# AmbaSat-08-GPS_TESEO.net
KiCad netlist of a schematic drawn in EAGLE
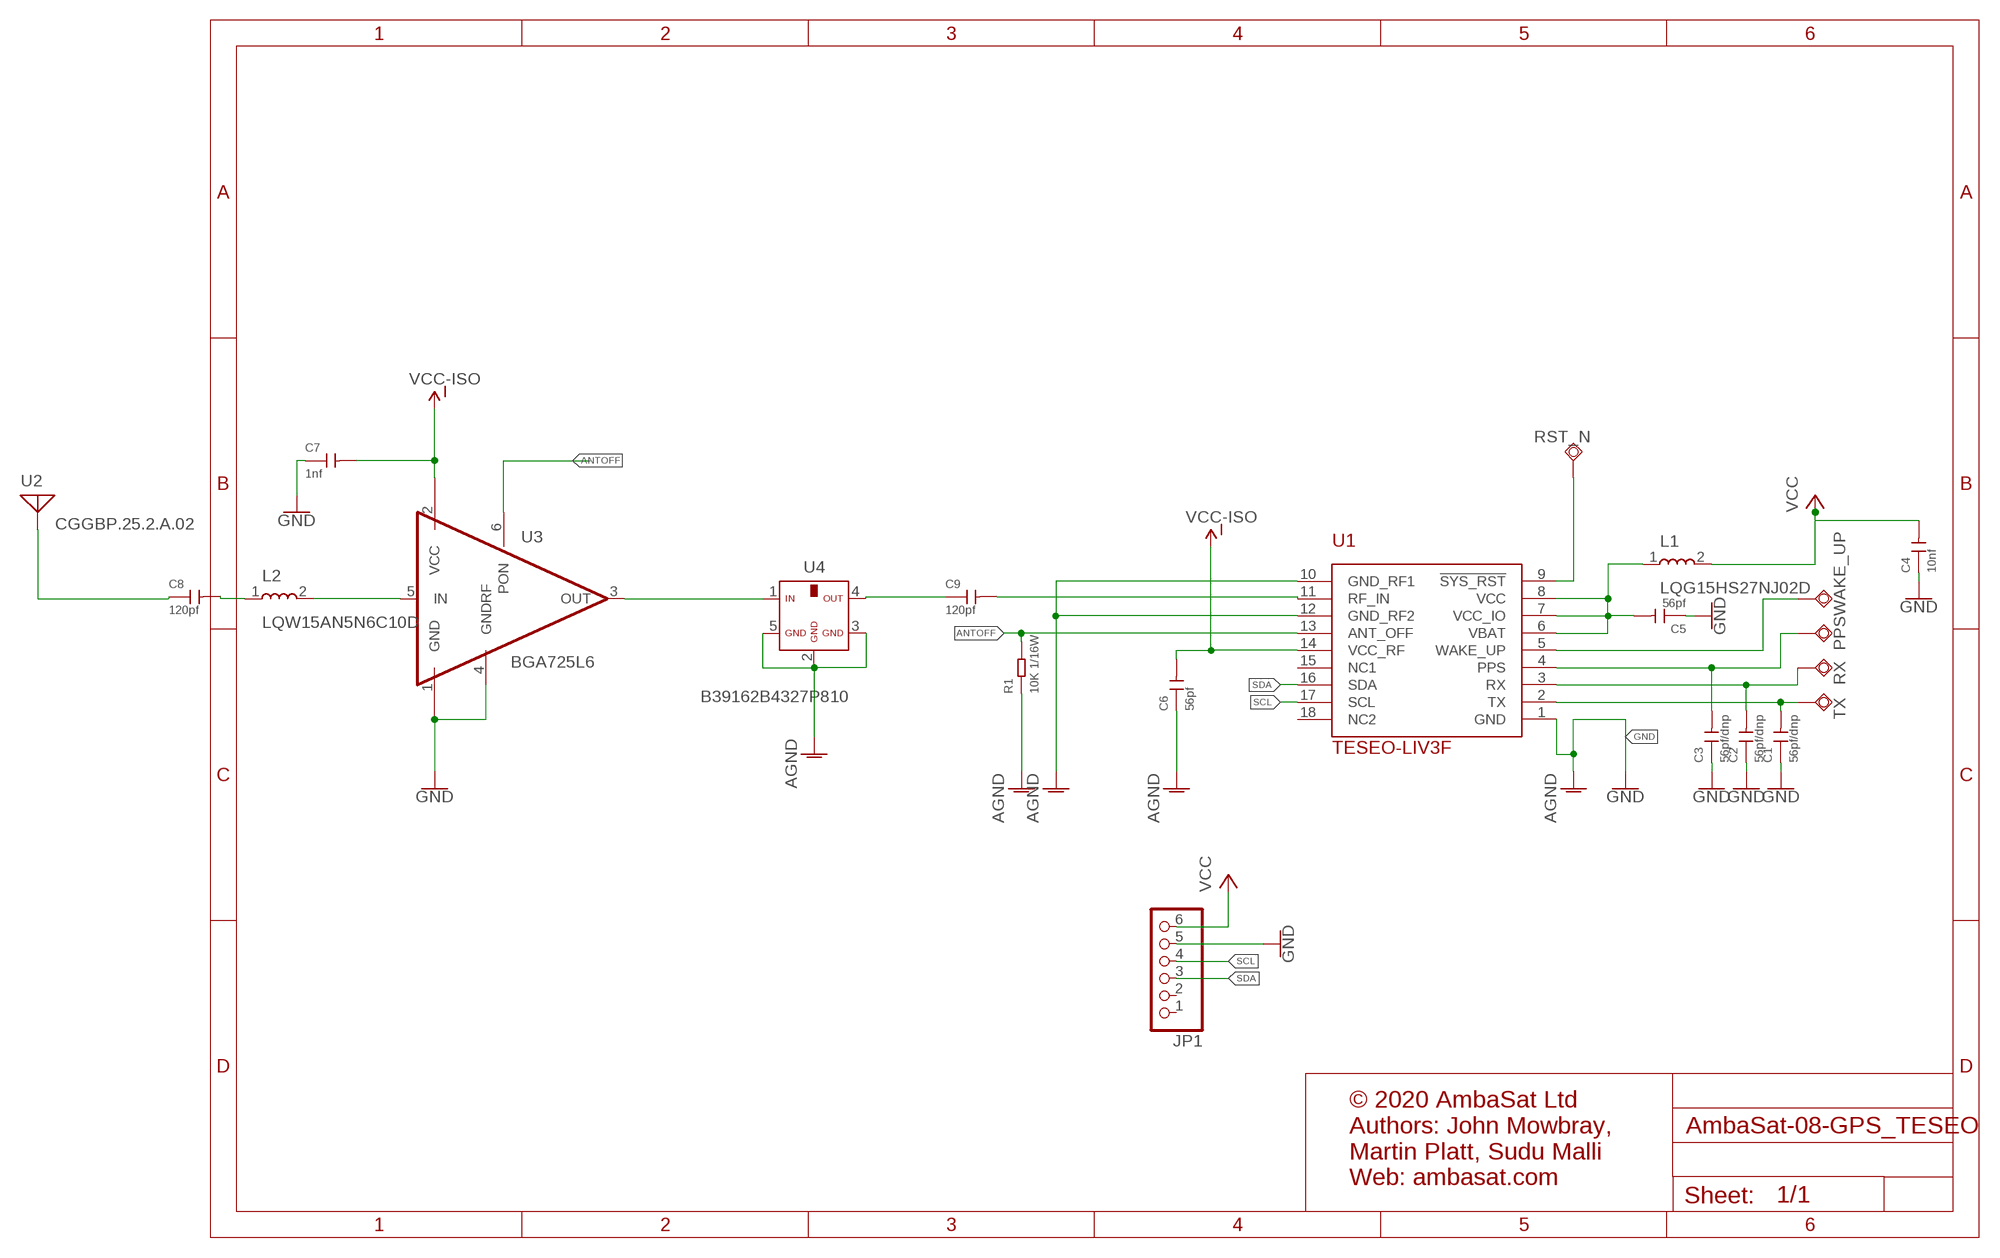
[diagram p0: schematic, sheet 1]

(export (version "E")
  (design (tool "Eeschema 10.0.6"))
  (components
    (comp (ref "C1")
      (value "56pf/dnp")
      (footprint "eagle-import:C0402")
      (fields (field (name "MPN") "CC0402JRNPO9BN101") (field (name "MPN_1") "CC0402JRNPO9BN560"))
      (libsource (lib "eagle-import") (part "CERAMIC-100PF-50V-5%-NPO(0402)"))
    )
    (comp (ref "C2")
      (value "56pf/dnp")
      (footprint "eagle-import:C0402")
      (fields (field (name "MPN") "CC0402JRNPO9BN101") (field (name "MPN_1") "CC0402JRNPO9BN560"))
      (libsource (lib "eagle-import") (part "CERAMIC-100PF-50V-5%-NPO(0402)"))
    )
    (comp (ref "C3")
      (value "56pf/dnp")
      (footprint "eagle-import:C0402")
      (fields (field (name "MPN") "CC0402JRNPO9BN101") (field (name "MPN_1") "CC0402JRNPO9BN560"))
      (libsource (lib "eagle-import") (part "CERAMIC-100PF-50V-5%-NPO(0402)"))
    )
    (comp (ref "C4")
      (value "10nf")
      (footprint "eagle-import:C0402")
      (fields (field (name "MPN") "CC0402KRX7R9BB103"))
      (libsource (lib "eagle-import") (part "CERAMIC-10NF-50V-10%-X7R(0402)"))
    )
    (comp (ref "C5")
      (value "56pf")
      (footprint "eagle-import:C0402")
      (fields (field (name "MPN") "CC0402JRNPO9BN101") (field (name "MPN_1") "CC0402JRNPO9BN560"))
      (libsource (lib "eagle-import") (part "CERAMIC-100PF-50V-5%-NPO(0402)"))
    )
    (comp (ref "C6")
      (value "56pf")
      (footprint "eagle-import:C0402")
      (fields (field (name "MPN") "CC0402JRNPO9BN101") (field (name "MPN_1") "CC0402JRNPO9BN560"))
      (libsource (lib "eagle-import") (part "CERAMIC-100PF-50V-5%-NPO(0402)"))
    )
    (comp (ref "C7")
      (value "1nf")
      (footprint "eagle-import:C0402")
      (fields (field (name "MPN") "CC0402KRX7R9BB102"))
      (libsource (lib "eagle-import") (part "CERAMIC-1NF-50V-10%-X7R(0402)"))
    )
    (comp (ref "C8")
      (value "120pf")
      (footprint "eagle-import:C0402")
      (fields (field (name "MPN") "CC0402JRNPO9BN101") (field (name "MPN_1") "CC0402JRNPO9BN121"))
      (libsource (lib "eagle-import") (part "CERAMIC-100PF-50V-5%-NPO(0402)"))
    )
    (comp (ref "C9")
      (value "120pf")
      (footprint "eagle-import:C0402")
      (fields (field (name "MPN") "CC0402JRNPO9BN101") (field (name "MPN_1") "CC0402JRNPO9BN121"))
      (libsource (lib "eagle-import") (part "CERAMIC-100PF-50V-5%-NPO(0402)"))
    )
    (comp (ref "JP1")
      (value "HEADER-1X6")
      (footprint "eagle-import:1X06_OVAL")
      (libsource (lib "eagle-import") (part "HEADER-1X6"))
    )
    (comp (ref "L1")
      (value "LQG15HS27NJ02D")
      (footprint "eagle-import:LQG15HN2N2S02D")
      (fields
        (field (name "DIGIKEY_PART_NUMBER") "490-1077-2-ND")
        (field (name "MANUFACTURER") "Murata Electronics North America")
        (field (name "MPN") "LQG15HN2N2S02D")
        (field (name "DIGIKEY_PART_NUMBER_1") "490-2628-1-ND")
        (field (name "MPN_1") "LQG15HS27NJ02D")
        (field (name "CREATED_BY") "PCBLayout.com")
      )
      (libsource (lib "eagle-import") (part "LQG15HN2N2S02D"))
    )
    (comp (ref "L2")
      (value "LQW15AN5N6C10D")
      (footprint "eagle-import:LQG15HN2N2S02D")
      (fields
        (field (name "DIGIKEY_PART_NUMBER") "490-1077-2-ND")
        (field (name "MANUFACTURER") "Murata Electronics North America")
        (field (name "MPN") "LQG15HN2N2S02D")
        (field (name "DIGIKEY_PART_NUMBER_1") "490-6833-1-ND")
        (field (name "MPN_1") "LQW15AN5N6C10D")
        (field (name "CREATED_BY") "PCBLayout.com")
      )
      (libsource (lib "eagle-import") (part "LQG15HN2N2S02D"))
    )
    (comp (ref "PPS")
      (value "TESTPAD_TPSQTP11SQ")
      (footprint "eagle-import:TESTPAD_TP11SQ")
      (libsource (lib "eagle-import") (part "TESTPAD_TPSQTP11SQ"))
    )
    (comp (ref "R1")
      (value "10K 1/16W")
      (footprint "eagle-import:R0402")
      (fields (field (name "MPN") "RC0402FR-0710KL"))
      (libsource (lib "eagle-import") (part "SMD-RES-10K-1%-1/16W(0402)"))
    )
    (comp (ref "RST_N")
      (value "TESTPAD_TPSQTP11SQ")
      (footprint "eagle-import:TESTPAD_TP11SQ")
      (libsource (lib "eagle-import") (part "TESTPAD_TPSQTP11SQ"))
    )
    (comp (ref "RX")
      (value "TESTPAD_TPSQTP11SQ")
      (footprint "eagle-import:TESTPAD_TP11SQ")
      (libsource (lib "eagle-import") (part "TESTPAD_TPSQTP11SQ"))
    )
    (comp (ref "TX")
      (value "TESTPAD_TPSQTP11SQ")
      (footprint "eagle-import:TESTPAD_TP11SQ")
      (libsource (lib "eagle-import") (part "TESTPAD_TPSQTP11SQ"))
    )
    (comp (ref "U1")
      (value "TESEO-LIV3F")
      (footprint "eagle-import:TESEO-LIV3F")
      (libsource (lib "eagle-import") (part "TESEO-LIV3F"))
    )
    (comp (ref "U2")
      (value "CGGBP.25.2.A.02")
      (footprint "eagle-import:ANTENNA-PATCH")
      (libsource (lib "eagle-import") (part "CGGBP.25.2.A.02"))
    )
    (comp (ref "U3")
      (value "BGA725L6")
      (footprint "eagle-import:PSON35P100X100X35-6N")
      (fields (field (name "MPN") "BGA725L6E6327FTSA1"))
      (libsource (lib "eagle-import") (part "BGA725L6"))
    )
    (comp (ref "U4")
      (value "B39162B4327P810")
      (footprint "eagle-import:FIL_B39162B9417K610")
      (libsource (lib "eagle-import") (part "B39162B4327P810"))
    )
    (comp (ref "WAKE_UP")
      (value "TESTPAD_TPSQTP11SQ")
      (footprint "eagle-import:TESTPAD_TP11SQ")
      (libsource (lib "eagle-import") (part "TESTPAD_TPSQTP11SQ"))
    )
  )
  (nets
    (net (code "1") (name "ANTOFF") (class "Default")
      (node (ref "R1") (pin "2") (pinfunction "2_2") (pintype "passive"))
      (node (ref "U1") (pin "13") (pinfunction "ANT_OFF_13") (pintype "output"))
      (node (ref "U3") (pin "6") (pinfunction "PON_6") (pintype "power_in"))
    )
    (net (code "2") (name "GND") (class "Default")
      (node (ref "C1") (pin "1") (pinfunction "1_1") (pintype "passive"))
      (node (ref "C2") (pin "1") (pinfunction "1_1") (pintype "passive"))
      (node (ref "C3") (pin "1") (pinfunction "1_1") (pintype "passive"))
      (node (ref "C4") (pin "1") (pinfunction "1_1") (pintype "passive"))
      (node (ref "C5") (pin "1") (pinfunction "1_1") (pintype "passive"))
      (node (ref "C6") (pin "1") (pinfunction "1_1") (pintype "passive"))
      (node (ref "C7") (pin "1") (pinfunction "1_1") (pintype "passive"))
      (node (ref "JP1") (pin "5") (pinfunction "5_5") (pintype "passive"))
      (node (ref "R1") (pin "1") (pinfunction "1_1") (pintype "passive"))
      (node (ref "U1") (pin "1") (pinfunction "GND_1") (pintype "power_in"))
      (node (ref "U1") (pin "10") (pinfunction "GND_RF1_10") (pintype "power_in"))
      (node (ref "U1") (pin "12") (pinfunction "GND_RF2_12") (pintype "power_in"))
      (node (ref "U3") (pin "1") (pinfunction "GND_1") (pintype "bidirectional"))
      (node (ref "U3") (pin "4") (pinfunction "GNDRF_4") (pintype "bidirectional"))
      (node (ref "U4") (pin "2") (pinfunction "GND3_2") (pintype "passive"))
      (node (ref "U4") (pin "3") (pinfunction "GND2_3") (pintype "passive"))
      (node (ref "U4") (pin "5") (pinfunction "GND_5") (pintype "passive"))
    )
    (net (code "3") (name "Net-(C8-Pad2)") (class "Default")
      (node (ref "C8") (pin "2") (pinfunction "2_2") (pintype "passive"))
      (node (ref "L2") (pin "1") (pinfunction "1_1") (pintype "passive"))
    )
    (net (code "4") (name "Net-(U1-PPS)") (class "Default")
      (node (ref "C3") (pin "2") (pinfunction "2_2") (pintype "passive"))
      (node (ref "PPS") (pin "TP") (pinfunction "TP_TP") (pintype "input"))
      (node (ref "U1") (pin "4") (pinfunction "PPS_4") (pintype "output"))
    )
    (net (code "5") (name "Net-(U1-RF_IN)") (class "Default")
      (node (ref "C9") (pin "2") (pinfunction "2_2") (pintype "passive"))
      (node (ref "U1") (pin "11") (pinfunction "RF_IN_11") (pintype "input"))
    )
    (net (code "6") (name "Net-(U1-RX)") (class "Default")
      (node (ref "C2") (pin "2") (pinfunction "2_2") (pintype "passive"))
      (node (ref "RX") (pin "TP") (pinfunction "TP_TP") (pintype "input"))
      (node (ref "U1") (pin "3") (pinfunction "RX_3") (pintype "bidirectional"))
    )
    (net (code "7") (name "Net-(U1-TX)") (class "Default")
      (node (ref "C1") (pin "2") (pinfunction "2_2") (pintype "passive"))
      (node (ref "TX") (pin "TP") (pinfunction "TP_TP") (pintype "input"))
      (node (ref "U1") (pin "2") (pinfunction "TX_2") (pintype "bidirectional"))
    )
    (net (code "8") (name "Net-(U1-VBAT)") (class "Default")
      (node (ref "C5") (pin "2") (pinfunction "2_2") (pintype "passive"))
      (node (ref "L1") (pin "1") (pinfunction "1_1") (pintype "passive"))
      (node (ref "U1") (pin "6") (pinfunction "VBAT_6") (pintype "power_in"))
      (node (ref "U1") (pin "7") (pinfunction "VCC_IO_7") (pintype "power_in"))
      (node (ref "U1") (pin "8") (pinfunction "VCC_8") (pintype "power_in"))
    )
    (net (code "9") (name "Net-(U1-WAKE_UP)") (class "Default")
      (node (ref "U1") (pin "5") (pinfunction "WAKE_UP_5") (pintype "input"))
      (node (ref "WAKE_UP") (pin "TP") (pinfunction "TP_TP") (pintype "input"))
    )
    (net (code "10") (name "Net-(U1-~{SYS_RST})") (class "Default")
      (node (ref "RST_N") (pin "TP") (pinfunction "TP_TP") (pintype "input"))
      (node (ref "U1") (pin "9") (pinfunction "~{SYS_RST}_9") (pintype "bidirectional"))
    )
    (net (code "11") (name "Net-(U2-1)") (class "Default")
      (node (ref "C8") (pin "1") (pinfunction "1_1") (pintype "passive"))
      (node (ref "U2") (pin "ANT") (pinfunction "1_ANT") (pintype "output"))
    )
    (net (code "12") (name "Net-(U3-IN)") (class "Default")
      (node (ref "L2") (pin "2") (pinfunction "2_2") (pintype "passive"))
      (node (ref "U3") (pin "5") (pinfunction "IN_5") (pintype "input"))
    )
    (net (code "13") (name "Net-(U3-OUT)") (class "Default")
      (node (ref "U3") (pin "3") (pinfunction "OUT_3") (pintype "output"))
      (node (ref "U4") (pin "1") (pinfunction "IN_1") (pintype "passive"))
    )
    (net (code "14") (name "Net-(U4-OUT)") (class "Default")
      (node (ref "C9") (pin "1") (pinfunction "1_1") (pintype "passive"))
      (node (ref "U4") (pin "4") (pinfunction "OUT_4") (pintype "passive"))
    )
    (net (code "15") (name "SCL") (class "Default")
      (node (ref "JP1") (pin "4") (pinfunction "4_4") (pintype "passive"))
      (node (ref "U1") (pin "17") (pinfunction "SCL_17") (pintype "bidirectional"))
    )
    (net (code "16") (name "SDA") (class "Default")
      (node (ref "JP1") (pin "3") (pinfunction "3_3") (pintype "passive"))
      (node (ref "U1") (pin "16") (pinfunction "SDA_16") (pintype "bidirectional"))
    )
    (net (code "17") (name "VCC") (class "Default")
      (node (ref "C4") (pin "2") (pinfunction "2_2") (pintype "passive"))
      (node (ref "JP1") (pin "6") (pinfunction "6_6") (pintype "passive"))
      (node (ref "L1") (pin "2") (pinfunction "2_2") (pintype "passive"))
    )
    (net (code "18") (name "VCC-ISO") (class "Default")
      (node (ref "C6") (pin "2") (pinfunction "2_2") (pintype "passive"))
      (node (ref "C7") (pin "2") (pinfunction "2_2") (pintype "passive"))
      (node (ref "U1") (pin "14") (pinfunction "VCC_RF_14") (pintype "power_in"))
      (node (ref "U3") (pin "2") (pinfunction "VCC_2") (pintype "bidirectional"))
    )
    (net (code "19") (name "unconnected-(JP1-Pad1)") (class "Default")
      (node (ref "JP1") (pin "1") (pinfunction "1_1") (pintype "passive"))
    )
    (net (code "20") (name "unconnected-(JP1-Pad2)") (class "Default")
      (node (ref "JP1") (pin "2") (pinfunction "2_2") (pintype "passive"))
    )
    (net (code "21") (name "unconnected-(U1-NC1-Pad15)") (class "Default")
      (node (ref "U1") (pin "15") (pinfunction "NC1_15") (pintype "no_connect"))
    )
    (net (code "22") (name "unconnected-(U1-NC2-Pad18)") (class "Default")
      (node (ref "U1") (pin "18") (pinfunction "NC2_18") (pintype "no_connect"))
    )
  )
)
